# rom.net
KiCad netlist of a schematic drawn in Altium Designer
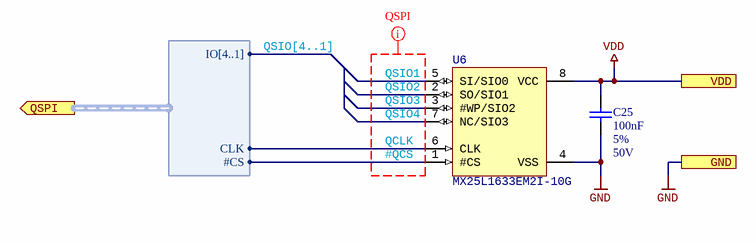
[diagram p0: rom.SchDoc]

(export (version "E")
  (design (tool "Eeschema 10.0.6"))
  (components
    (comp (ref "C25")
      (value "100nF")
      (footprint "CAPC1608N")
      (description "Capacitor")
      (fields (field (name "TOLERANCE") "5%") (field (name "VOLTAGE") "50V"))
      (libsource (lib "passives") (part "Capacitor"))
    )
    (comp (ref "U6")
      (value "MX25L1633EM2I-10G")
      (footprint "SOIC-8-WIDE")
      (description "16M-BIT [x 1/x 2/x 4] CMOS MXSMIO  (SERIAL MULTI I/O) FLASH MEMORY")
      (libsource (lib "mem") (part "MX25L1633E"))
    )
  )
  (nets
    (net (code "2") (name "/#QCS") (class "Default")
      (node (ref "U6") (pin "1") (pinfunction "#CS_1") (pintype "input"))
    )
    (net (code "3") (name "/QCLK") (class "Default")
      (node (ref "U6") (pin "6") (pinfunction "CLK_6") (pintype "input"))
    )
    (net (code "4") (name "/QSIO1") (class "Default")
      (node (ref "U6") (pin "5") (pinfunction "SI/SIO0_5") (pintype "bidirectional"))
    )
    (net (code "5") (name "/QSIO2") (class "Default")
      (node (ref "U6") (pin "2") (pinfunction "SO/SIO1_2") (pintype "bidirectional"))
    )
    (net (code "6") (name "/QSIO3") (class "Default")
      (node (ref "U6") (pin "3") (pinfunction "#WP/SIO2_3") (pintype "bidirectional"))
    )
    (net (code "7") (name "/QSIO4") (class "Default")
      (node (ref "U6") (pin "7") (pinfunction "NC/SIO3_7") (pintype "bidirectional"))
    )
    (net (code "10") (name "GND") (class "Default")
      (node (ref "C25") (pin "1") (pinfunction "1_1") (pintype "passive"))
      (node (ref "U6") (pin "4") (pinfunction "VSS_4") (pintype "power_in"))
    )
    (net (code "11") (name "VDD") (class "Default")
      (node (ref "C25") (pin "2") (pinfunction "2_2") (pintype "passive"))
      (node (ref "U6") (pin "8") (pinfunction "VCC_8") (pintype "power_in"))
    )
  )
)
